# OZ440-SE110-CAR001-SCH2.net
KiCad netlist of a schematic drawn in Altium Designer
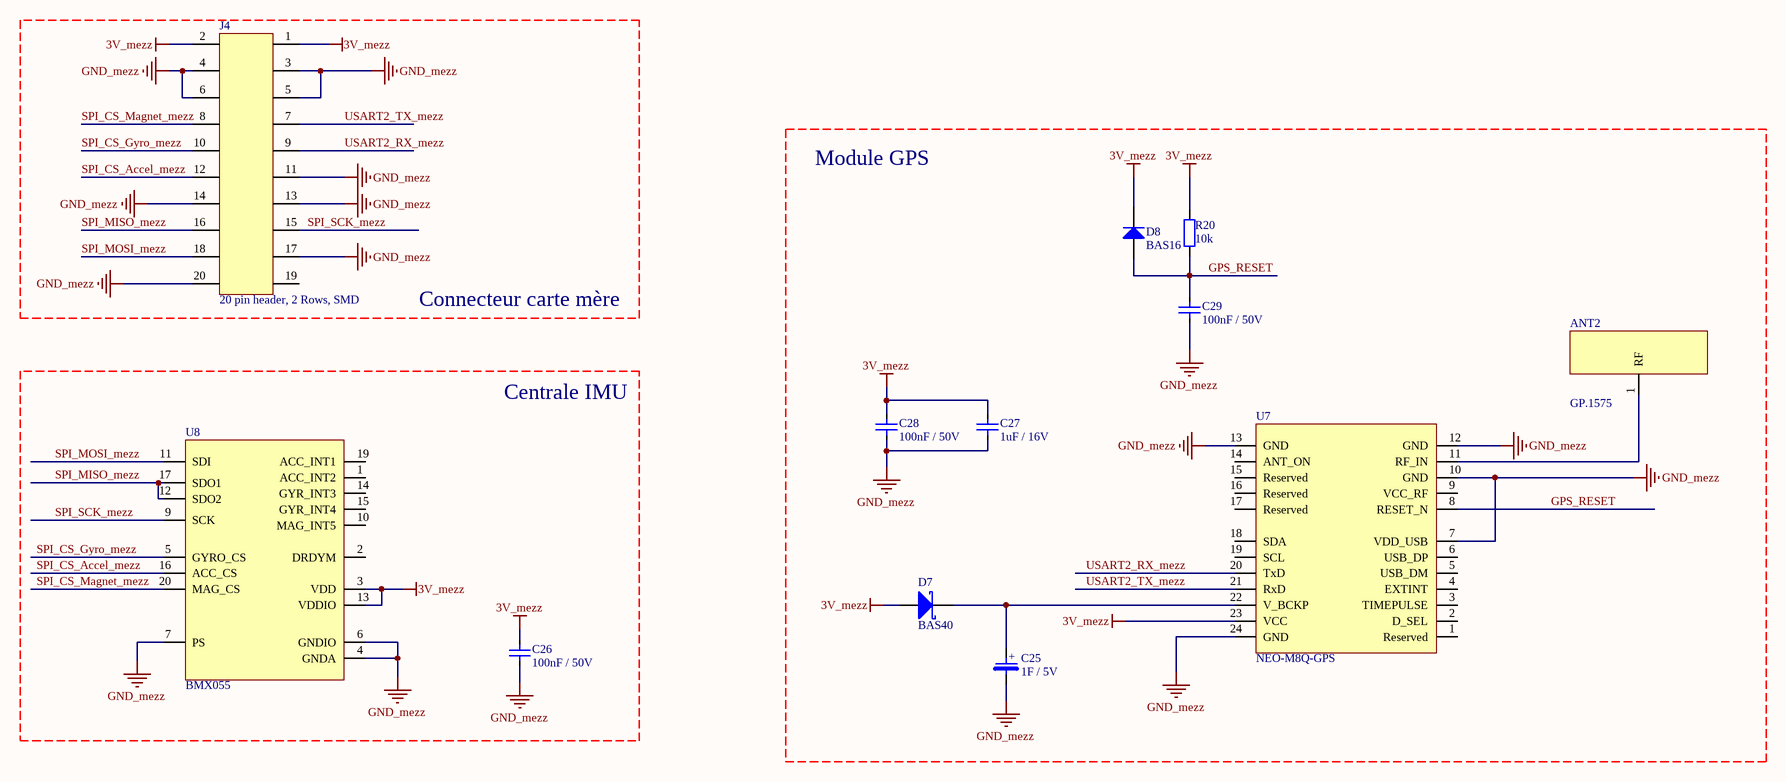
[diagram p0: OZ440-SE110-CAR001-SCH2.SchDoc]

(export (version "E")
  (design (tool "Eeschema 10.0.6"))
  (components
    (comp (ref "ANT2")
      (value "ANT-STD-GPS")
      (footprint "ANT_SMD-SPE-GP_1575")
      (description "35mm GPS patch antenna")
      (fields (field (name "DISPLAYED REFERENCE") "GP.1575") (field (name "MANUFACTURER") "Taoglass"))
      (libsource (lib "lib_NAIO") (part "ANT-STD-GPS"))
    )
    (comp (ref "C25")
      (value "CAP-POL-SMD")
      (footprint "RADIAL-STD-P20-H5-D20")
      (description "1F 5V capacitor")
      (fields
        (field (name "DISPLAYED REFERENCE") "1F / 5V")
        (field (name "MANUFACTURER") "Cornell Dubillier")
      )
      (libsource (lib "lib_NAIO") (part "CAP-POL-SMD"))
    )
    (comp (ref "C26")
      (value "CAP-SMD")
      (footprint "C0805-STD")
      (description "0805 100nF / 50V  X7R ceramic capacitor")
      (fields
        (field (name "DISPLAYED REFERENCE") "100nF / 50V")
        (field (name "TOLERANCE") "+/- 10%")
        (field (name "MANUFACTURER") "vishay")
      )
      (libsource (lib "lib_NAIO") (part "CAP-SMD"))
    )
    (comp (ref "C27")
      (value "CAP-SMD")
      (footprint "C0805-STD")
      (description "0805 1uF / 16V X7R ceramic capacitor")
      (fields
        (field (name "DISPLAYED REFERENCE") "1uF / 16V")
        (field (name "TOLERANCE") "+/- 10%")
        (field (name "MANUFACTURER") "Kemet")
      )
      (libsource (lib "lib_NAIO") (part "CAP-SMD"))
    )
    (comp (ref "C28")
      (value "CAP-SMD")
      (footprint "C0805-STD")
      (description "0805 100nF / 50V  X7R ceramic capacitor")
      (fields
        (field (name "DISPLAYED REFERENCE") "100nF / 50V")
        (field (name "TOLERANCE") "+/- 10%")
        (field (name "MANUFACTURER") "vishay")
      )
      (libsource (lib "lib_NAIO") (part "CAP-SMD"))
    )
    (comp (ref "C29")
      (value "CAP-SMD")
      (footprint "C0805-STD")
      (description "0805 100nF / 50V  X7R ceramic capacitor")
      (fields
        (field (name "DISPLAYED REFERENCE") "100nF / 50V")
        (field (name "TOLERANCE") "+/- 10%")
        (field (name "MANUFACTURER") "vishay")
      )
      (libsource (lib "lib_NAIO") (part "CAP-SMD"))
    )
    (comp (ref "D7")
      (value "BAS40-SOT23")
      (footprint "SOT23-STD")
      (description "40V / 120mA signal schottky diode")
      (fields (field (name "DISPLAYED REFERENCE") "BAS40") (field (name "MANUFACTURER") "NXP"))
      (libsource (lib "lib_NAIO") (part "BAS40-SOT23"))
    )
    (comp (ref "D8")
      (value "BAS16-SOT23")
      (footprint "SOT23-STD")
      (description "100V / 120mA signal  diode")
      (fields (field (name "DISPLAYED REFERENCE") "BAS16") (field (name "MANUFACTURER") "NXP"))
      (libsource (lib "lib_NAIO") (part "BAS16-SOT23"))
    )
    (comp (ref "J4")
      (value "CONN-STD-20P_2ROW")
      (footprint "CONN-SPE_TSM110-02-T")
      (description "20 pin header, 2.54mm, SMD")
      (fields
        (field (name "DISPLAYED REFERENCE") "20 pin header, 2 Rows, SMD")
        (field (name "MANUFACTURER") "SAMTEC")
      )
      (libsource (lib "lib_NAIO") (part "CONN-STD-20P_2ROW"))
    )
    (comp (ref "R20")
      (value "RES-SMD")
      (footprint "R0805-STD")
      (description "10k Ohm 0805 SMD resistor")
      (fields
        (field (name "DISPLAYED REFERENCE") "10k")
        (field (name "TOLERANCE") "1 %")
        (field (name "MANUFACTURER") "Vishay")
      )
      (libsource (lib "lib_NAIO") (part "RES-SMD"))
    )
    (comp (ref "U7")
      (value "~")
      (footprint "SMD24-SPE-NEO7")
      (description "Neo 8 GPS module")
      (fields (field (name "DISPLAYED REFERENCE") "NEO-M8Q-GPS") (field (name "MANUFACTURER") "Ublox"))
      (libsource (lib "lib_NAIO") (part "NEO_7-SMD24"))
    )
    (comp (ref "U8")
      (value "BMX055-LGA20")
      (footprint "LGA20-SPE-BMX055")
      (description "9 axis SPI IMU sensor")
      (fields (field (name "DISPLAYED REFERENCE") "BMX055") (field (name "MANUFACTURER") "Bosch"))
      (libsource (lib "lib_NAIO") (part "BMX055-LGA20"))
    )
  )
  (nets
    (net (code "1") (name "/GPS_RESET") (class "Default")
      (node (ref "C29") (pin "2") (pinfunction "2_2") (pintype "passive"))
      (node (ref "D8") (pin "1") (pinfunction "A_1") (pintype "passive"))
      (node (ref "R20") (pin "1") (pinfunction "1_1") (pintype "passive"))
      (node (ref "U7") (pin "8") (pinfunction "RESET_N_8") (pintype "passive"))
    )
    (net (code "2") (name "/SPI_CS_Accel_mezz") (class "Default")
      (node (ref "J4") (pin "12") (pinfunction "12_12") (pintype "passive"))
      (node (ref "U8") (pin "16") (pinfunction "ACC_CS_16") (pintype "passive"))
    )
    (net (code "3") (name "/SPI_CS_Gyro_mezz") (class "Default")
      (node (ref "J4") (pin "10") (pinfunction "10_10") (pintype "passive"))
      (node (ref "U8") (pin "5") (pinfunction "GYRO_CS_5") (pintype "passive"))
    )
    (net (code "4") (name "/SPI_CS_Magnet_mezz") (class "Default")
      (node (ref "J4") (pin "8") (pinfunction "8_8") (pintype "passive"))
      (node (ref "U8") (pin "20") (pinfunction "MAG_CS_20") (pintype "passive"))
    )
    (net (code "5") (name "/SPI_MISO_mezz") (class "Default")
      (node (ref "J4") (pin "16") (pinfunction "16_16") (pintype "passive"))
      (node (ref "U8") (pin "12") (pinfunction "SDO2_12") (pintype "passive"))
      (node (ref "U8") (pin "17") (pinfunction "SDO1_17") (pintype "passive"))
    )
    (net (code "6") (name "/SPI_MOSI_mezz") (class "Default")
      (node (ref "J4") (pin "18") (pinfunction "18_18") (pintype "passive"))
      (node (ref "U8") (pin "11") (pinfunction "SDI_11") (pintype "passive"))
    )
    (net (code "7") (name "/SPI_SCK_mezz") (class "Default")
      (node (ref "J4") (pin "15") (pinfunction "15_15") (pintype "passive"))
      (node (ref "U8") (pin "9") (pinfunction "SCK_9") (pintype "passive"))
    )
    (net (code "8") (name "/USART2_RX_mezz") (class "Default")
      (node (ref "J4") (pin "9") (pinfunction "9_9") (pintype "passive"))
      (node (ref "U7") (pin "20") (pinfunction "TxD_20") (pintype "passive"))
    )
    (net (code "9") (name "/USART2_TX_mezz") (class "Default")
      (node (ref "J4") (pin "7") (pinfunction "7_7") (pintype "passive"))
      (node (ref "U7") (pin "21") (pinfunction "RxD_21") (pintype "passive"))
    )
    (net (code "10") (name "3V_mezz") (class "Default")
      (node (ref "C26") (pin "2") (pinfunction "2_2") (pintype "passive"))
      (node (ref "C27") (pin "2") (pinfunction "2_2") (pintype "passive"))
      (node (ref "C28") (pin "2") (pinfunction "2_2") (pintype "passive"))
      (node (ref "D7") (pin "1") (pinfunction "A_1") (pintype "passive"))
      (node (ref "D8") (pin "3") (pinfunction "K_3") (pintype "passive"))
      (node (ref "J4") (pin "1") (pinfunction "1_1") (pintype "passive"))
      (node (ref "J4") (pin "2") (pinfunction "2_2") (pintype "passive"))
      (node (ref "R20") (pin "2") (pinfunction "2_2") (pintype "passive"))
      (node (ref "U7") (pin "23") (pinfunction "VCC_23") (pintype "passive"))
      (node (ref "U8") (pin "13") (pinfunction "VDDIO_13") (pintype "passive"))
      (node (ref "U8") (pin "3") (pinfunction "VDD_3") (pintype "passive"))
    )
    (net (code "11") (name "GND_mezz") (class "Default")
      (node (ref "C25") (pin "2") (pinfunction "2_2") (pintype "passive"))
      (node (ref "C26") (pin "1") (pinfunction "1_1") (pintype "passive"))
      (node (ref "C27") (pin "1") (pinfunction "1_1") (pintype "passive"))
      (node (ref "C28") (pin "1") (pinfunction "1_1") (pintype "passive"))
      (node (ref "C29") (pin "1") (pinfunction "1_1") (pintype "passive"))
      (node (ref "J4") (pin "11") (pinfunction "11_11") (pintype "passive"))
      (node (ref "J4") (pin "13") (pinfunction "13_13") (pintype "passive"))
      (node (ref "J4") (pin "14") (pinfunction "14_14") (pintype "passive"))
      (node (ref "J4") (pin "17") (pinfunction "17_17") (pintype "passive"))
      (node (ref "J4") (pin "20") (pinfunction "20_20") (pintype "passive"))
      (node (ref "J4") (pin "3") (pinfunction "3_3") (pintype "passive"))
      (node (ref "J4") (pin "4") (pinfunction "4_4") (pintype "passive"))
      (node (ref "J4") (pin "5") (pinfunction "5_5") (pintype "passive"))
      (node (ref "J4") (pin "6") (pinfunction "6_6") (pintype "passive"))
      (node (ref "U7") (pin "10") (pinfunction "GND_10") (pintype "passive"))
      (node (ref "U7") (pin "12") (pinfunction "GND_12") (pintype "passive"))
      (node (ref "U7") (pin "13") (pinfunction "GND_13") (pintype "passive"))
      (node (ref "U7") (pin "24") (pinfunction "GND_24") (pintype "passive"))
      (node (ref "U7") (pin "7") (pinfunction "VDD_USB_7") (pintype "passive"))
      (node (ref "U8") (pin "4") (pinfunction "GNDA_4") (pintype "passive"))
      (node (ref "U8") (pin "6") (pinfunction "GNDIO_6") (pintype "passive"))
      (node (ref "U8") (pin "7") (pinfunction "PS_7") (pintype "passive"))
    )
    (net (code "12") (name "Net-(ANT2-RF)") (class "Default")
      (node (ref "ANT2") (pin "1") (pinfunction "RF_1") (pintype "passive"))
      (node (ref "U7") (pin "11") (pinfunction "RF_IN_11") (pintype "passive"))
    )
    (net (code "13") (name "Net-(D7-K)") (class "Default")
      (node (ref "C25") (pin "1") (pinfunction "1_1") (pintype "passive"))
      (node (ref "D7") (pin "3") (pinfunction "K_3") (pintype "passive"))
      (node (ref "U7") (pin "22") (pinfunction "V_BCKP_22") (pintype "passive"))
    )
    (net (code "14") (name "unconnected-(J4-Pad19)") (class "Default")
      (node (ref "J4") (pin "19") (pinfunction "19_19") (pintype "passive"))
    )
    (net (code "15") (name "unconnected-(U7-ANT_ON-Pad14)") (class "Default")
      (node (ref "U7") (pin "14") (pinfunction "ANT_ON_14") (pintype "passive"))
    )
    (net (code "16") (name "unconnected-(U7-D_SEL-Pad2)") (class "Default")
      (node (ref "U7") (pin "2") (pinfunction "D_SEL_2") (pintype "passive"))
    )
    (net (code "17") (name "unconnected-(U7-EXTINT-Pad4)") (class "Default")
      (node (ref "U7") (pin "4") (pinfunction "EXTINT_4") (pintype "passive"))
    )
    (net (code "18") (name "unconnected-(U7-Reserved-Pad1)") (class "Default")
      (node (ref "U7") (pin "1") (pinfunction "Reserved_1") (pintype "passive"))
    )
    (net (code "19") (name "unconnected-(U7-Reserved-Pad15)") (class "Default")
      (node (ref "U7") (pin "15") (pinfunction "Reserved_15") (pintype "passive"))
    )
    (net (code "20") (name "unconnected-(U7-Reserved-Pad16)") (class "Default")
      (node (ref "U7") (pin "16") (pinfunction "Reserved_16") (pintype "passive"))
    )
    (net (code "21") (name "unconnected-(U7-Reserved-Pad17)") (class "Default")
      (node (ref "U7") (pin "17") (pinfunction "Reserved_17") (pintype "passive"))
    )
    (net (code "22") (name "unconnected-(U7-SCL-Pad19)") (class "Default")
      (node (ref "U7") (pin "19") (pinfunction "SCL_19") (pintype "passive"))
    )
    (net (code "23") (name "unconnected-(U7-SDA-Pad18)") (class "Default")
      (node (ref "U7") (pin "18") (pinfunction "SDA_18") (pintype "passive"))
    )
    (net (code "24") (name "unconnected-(U7-TIMEPULSE-Pad3)") (class "Default")
      (node (ref "U7") (pin "3") (pinfunction "TIMEPULSE_3") (pintype "passive"))
    )
    (net (code "25") (name "unconnected-(U7-USB_DM-Pad5)") (class "Default")
      (node (ref "U7") (pin "5") (pinfunction "USB_DM_5") (pintype "passive"))
    )
    (net (code "26") (name "unconnected-(U7-USB_DP-Pad6)") (class "Default")
      (node (ref "U7") (pin "6") (pinfunction "USB_DP_6") (pintype "passive"))
    )
    (net (code "27") (name "unconnected-(U7-VCC_RF-Pad9)") (class "Default")
      (node (ref "U7") (pin "9") (pinfunction "VCC_RF_9") (pintype "passive"))
    )
    (net (code "28") (name "unconnected-(U8-ACC_INT1-Pad19)") (class "Default")
      (node (ref "U8") (pin "19") (pinfunction "ACC_INT1_19") (pintype "passive"))
    )
    (net (code "29") (name "unconnected-(U8-ACC_INT2-Pad1)") (class "Default")
      (node (ref "U8") (pin "1") (pinfunction "ACC_INT2_1") (pintype "passive"))
    )
    (net (code "30") (name "unconnected-(U8-DRDYM-Pad2)") (class "Default")
      (node (ref "U8") (pin "2") (pinfunction "DRDYM_2") (pintype "passive"))
    )
    (net (code "31") (name "unconnected-(U8-GYR_INT3-Pad14)") (class "Default")
      (node (ref "U8") (pin "14") (pinfunction "GYR_INT3_14") (pintype "passive"))
    )
    (net (code "32") (name "unconnected-(U8-GYR_INT4-Pad15)") (class "Default")
      (node (ref "U8") (pin "15") (pinfunction "GYR_INT4_15") (pintype "passive"))
    )
    (net (code "33") (name "unconnected-(U8-MAG_INT5-Pad10)") (class "Default")
      (node (ref "U8") (pin "10") (pinfunction "MAG_INT5_10") (pintype "passive"))
    )
  )
)
